# phase.net
KiCad netlist of a schematic drawn in Altium Designer
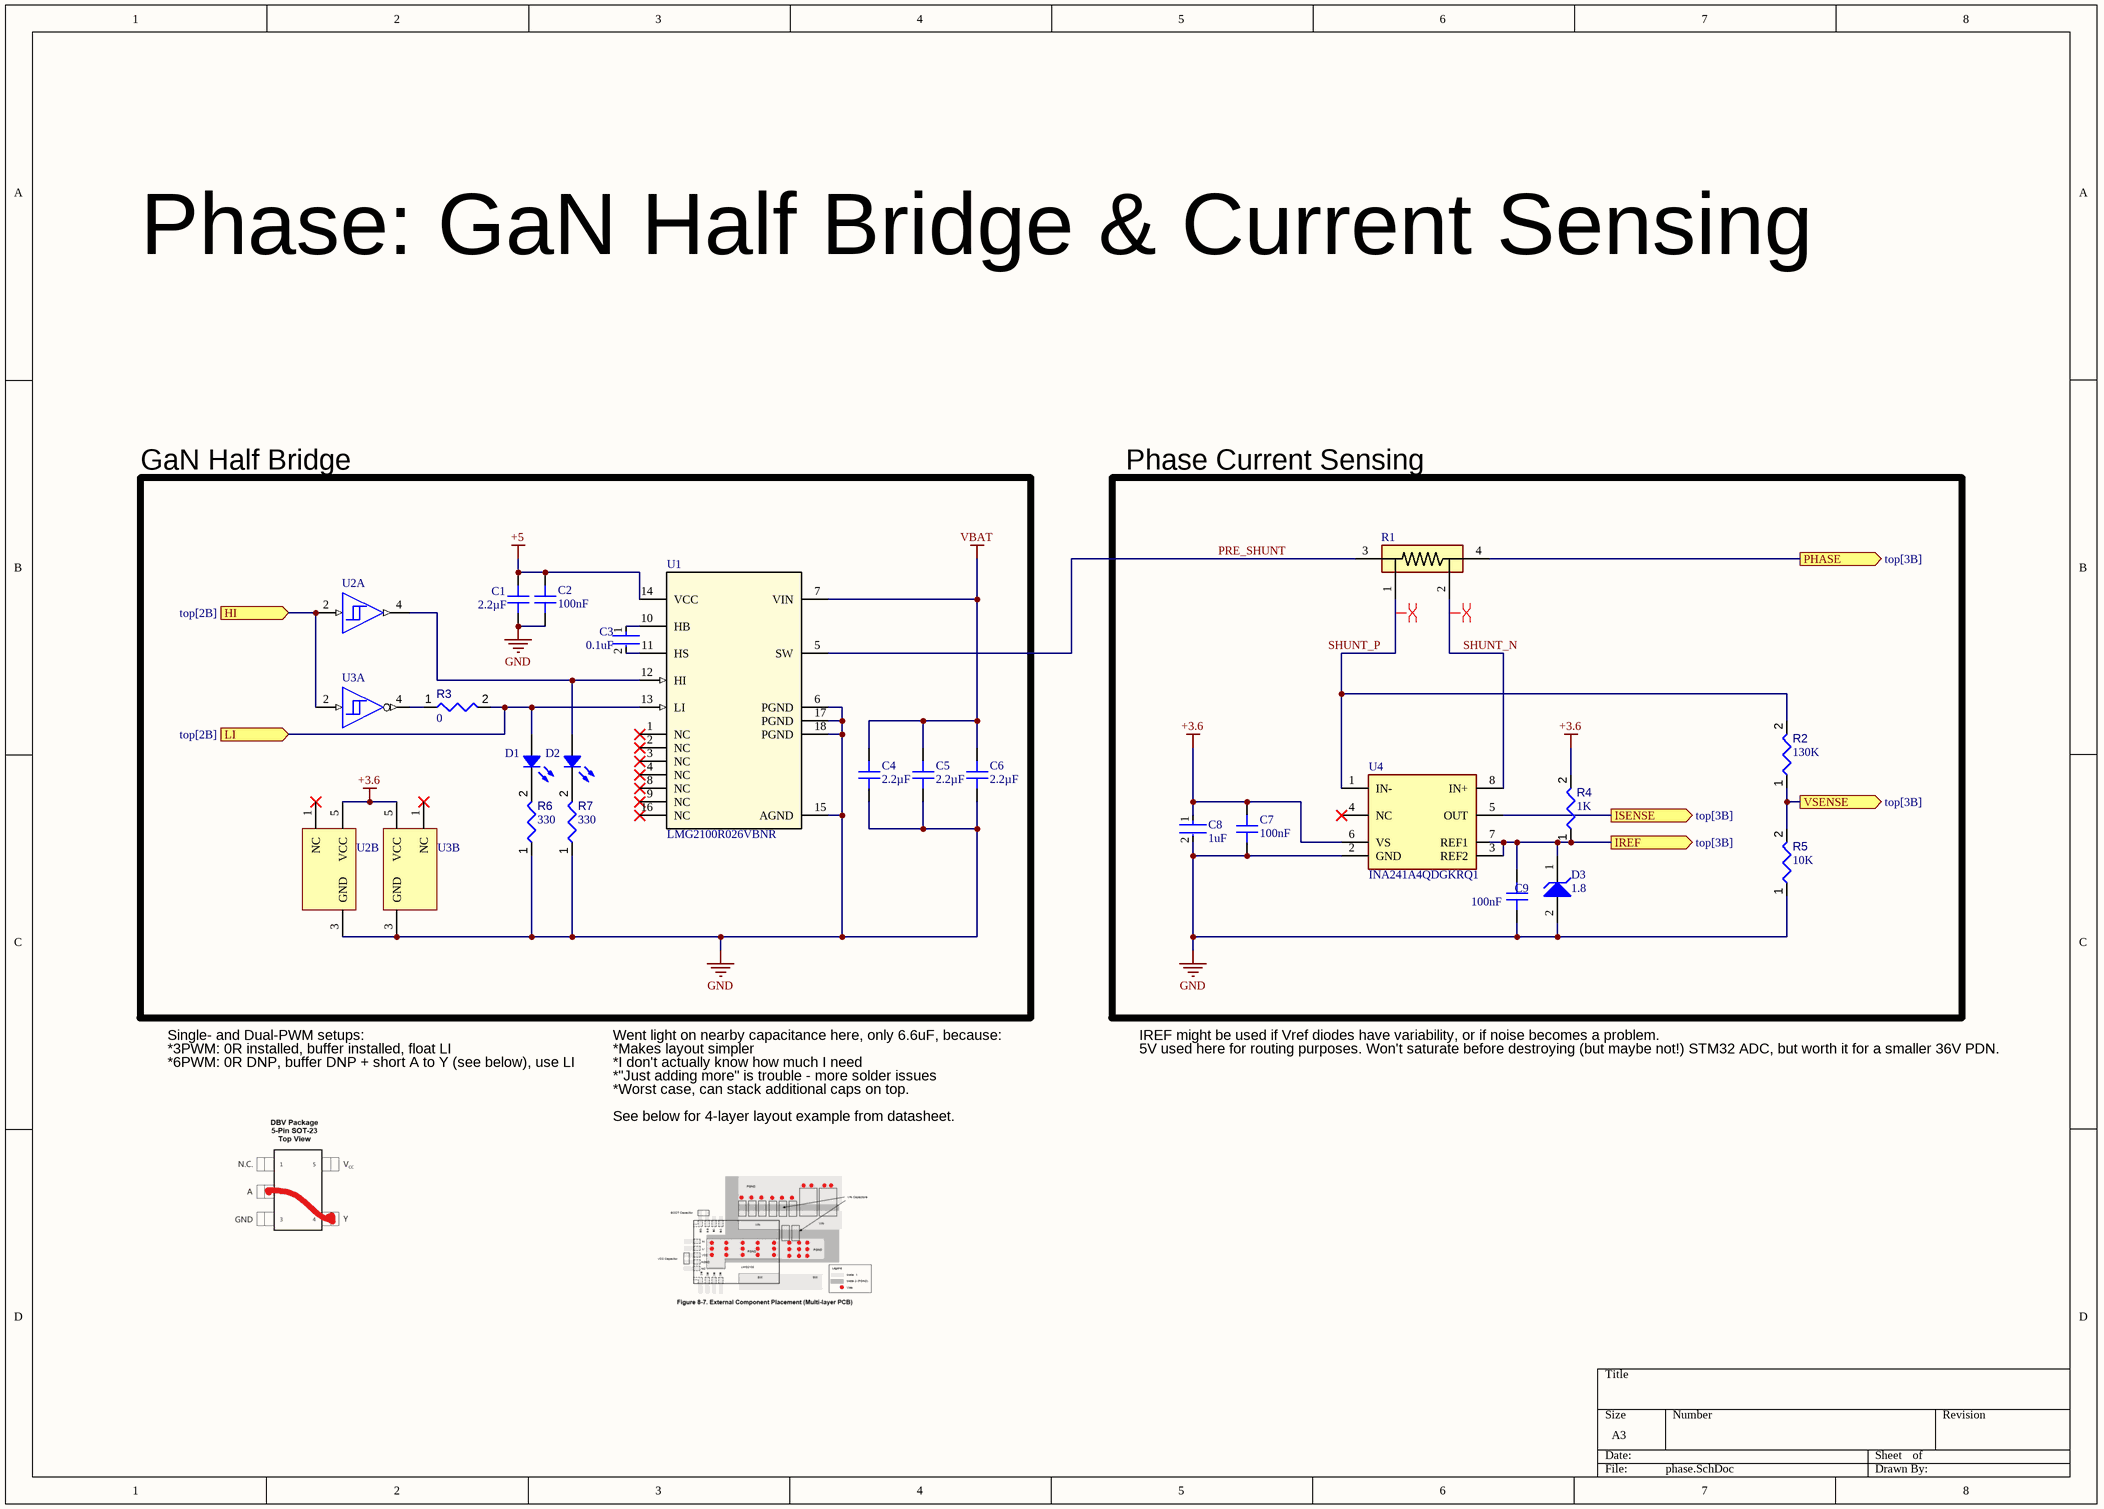
[diagram p0: phase.SchDoc]

(export (version "E")
  (design (tool "Eeschema 10.0.6"))
  (components
    (comp (ref "C1")
      (value "2.2µF")
      (footprint "CAP 0603_1608")
      (description "CAP CER 2.2UF 16V X5R 0603")
      (fields (field (name "PART NUMBER") "KGM15BR51C225KM") (field (name "TOLERANCE") "10%"))
      (libsource (lib "Americas- Northwestern Formula Racing- Northwestern University") (part "CAPACITOR"))
    )
    (comp (ref "C2")
      (value "100nF")
      (footprint "CAPC0402(1005)33_L")
      (description "CAP CER 0.1UF 16V X7R 0402")
      (fields
        (field (name "MANUFACTURER") "Samsung Electro-Mechanics")
        (field (name "PART NUMBER") "CL05B104KO5NNNC")
      )
      (libsource (lib "Americas- Northwestern Formula Racing- Northwestern University") (part "CAPACITOR"))
    )
    (comp (ref "C3")
      (value "0.1uF")
      (footprint "FP-GRM155-0_05-MFG")
      (description "Chip Multilayer Ceramic Capacitors for General Purpose, 0402, 1.0uF, B, 10%, 20%, 16V")
      (libsource (lib "Altium Content Vault") (part "02cd4be3c70576c341d710602a673aa"))
    )
    (comp (ref "C4")
      (value "2.2µF")
      (footprint "MURATA GRM21B 0805_2012")
      (description "CAP CER 2.2UF 100V X7T 0805")
      (fields (field (name "TOLERANCE") "20%") (field (name "MANUFACTURER") "Murata Electronics"))
      (libsource (lib "Americas- Northwestern Formula Racing- Northwestern University") (part "CAPACITOR"))
    )
    (comp (ref "C5")
      (value "2.2µF")
      (footprint "MURATA GRM21B 0805_2012")
      (description "CAP CER 2.2UF 100V X7T 0805")
      (fields (field (name "TOLERANCE") "20%") (field (name "MANUFACTURER") "Murata Electronics"))
      (libsource (lib "Americas- Northwestern Formula Racing- Northwestern University") (part "CAPACITOR"))
    )
    (comp (ref "C6")
      (value "2.2µF")
      (footprint "MURATA GRM21B 0805_2012")
      (description "CAP CER 2.2UF 100V X7T 0805")
      (fields (field (name "TOLERANCE") "20%") (field (name "MANUFACTURER") "Murata Electronics"))
      (libsource (lib "Americas- Northwestern Formula Racing- Northwestern University") (part "CAPACITOR"))
    )
    (comp (ref "C7")
      (value "100nF")
      (footprint "CAPC0402(1005)33_L")
      (description "CAP CER 0.1UF 16V X7R 0402")
      (fields
        (field (name "MANUFACTURER") "Samsung Electro-Mechanics")
        (field (name "PART NUMBER") "CL05B104KO5NNNC")
      )
      (libsource (lib "Americas- Northwestern Formula Racing- Northwestern University") (part "CAPACITOR"))
    )
    (comp (ref "C8")
      (value "1uF")
      (footprint "FP-GRM155-0_05-MFG")
      (description "Chip Multilayer Ceramic Capacitors for General Purpose, 0402, 1.0uF, B, 10%, 20%, 16V")
      (libsource (lib "Altium Content Vault") (part "02cd4be3c70576c341d710602a673aa"))
    )
    (comp (ref "C9")
      (value "100nF")
      (footprint "CAPC0402(1005)33_L")
      (description "CAP CER 0.1UF 16V X7R 0402")
      (fields
        (field (name "MANUFACTURER") "Samsung Electro-Mechanics")
        (field (name "PART NUMBER") "CL05B104KO5NNNC")
      )
      (libsource (lib "Americas- Northwestern Formula Racing- Northwestern University") (part "CAPACITOR"))
    )
    (comp (ref "D1")
      (value "150060BS55040")
      (footprint "LED 0603_1608 BLUE")
      (description "LED BLUE DIFFUSED 0603 SMD")
      (fields (field (name "MANUFACTURER") "Würth Elektronik"))
      (libsource (lib "Americas- Northwestern Formula Racing- Northwestern University") (part "LED"))
    )
    (comp (ref "D2")
      (value "150060BS55040")
      (footprint "LED 0603_1608 BLUE")
      (description "LED BLUE DIFFUSED 0603 SMD")
      (fields (field (name "MANUFACTURER") "Würth Elektronik"))
      (libsource (lib "Americas- Northwestern Formula Racing- Northwestern University") (part "LED"))
    )
    (comp (ref "D3")
      (value "SZMMSZ4678T1G")
      (footprint "ONSC-SOD-123-2-425-04_V")
      (description "Zener Voltage Regulator, 500 mW, 2-Pin SOD-123, Pb-Free, Tape and Reel")
      (fields (field (name "VZ TYP (V)") "1.8") (field (name "MANUFACTURER") "On Semiconductor"))
      (libsource (lib "Altium Content Vault") (part "ONSC-K1A2-2"))
    )
    (comp (ref "R1")
      (value "PU2726FKMPD0U3L")
      (footprint "PU2726FKMPD0U3L")
      (description "Thick Film Resistors - SMD 0.3mOhms 11W 2726 1% 75ppm Shunt AEC-Q200")
      (libsource (lib "Americas- Northwestern Formula Racing- Northwestern University") (part "PU2726FKMPD0U3L"))
    )
    (comp (ref "R2")
      (value "130K")
      (footprint "RESC0603(1608)_L")
      (description "120R 0.1W 5% 0603 (1608 Metric)  SMD")
      (fields (field (name "POWER") "100mW") (field (name "TOLERANCE") "5%"))
      (libsource (lib "Americas- Northwestern Formula Racing- Northwestern University") (part "120R3J"))
    )
    (comp (ref "R3")
      (value "0")
      (footprint "RESC0603(1608)_L")
      (description "Jumper 0603 (1608 Metric)")
      (fields (field (name "Comment") "0R3J"))
      (libsource (lib "Americas- Northwestern Formula Racing- Northwestern University") (part "0R3J"))
    )
    (comp (ref "R4")
      (value "1K")
      (footprint "RESC0603(1608)_L")
      (description "120R 0.1W 5% 0603 (1608 Metric)  SMD")
      (fields (field (name "POWER") "100mW") (field (name "TOLERANCE") "5%"))
      (libsource (lib "Americas- Northwestern Formula Racing- Northwestern University") (part "120R3J"))
    )
    (comp (ref "R5")
      (value "10K")
      (footprint "RESC0603(1608)_L")
      (description "120R 0.1W 5% 0603 (1608 Metric)  SMD")
      (fields (field (name "POWER") "100mW") (field (name "TOLERANCE") "5%"))
      (libsource (lib "Americas- Northwestern Formula Racing- Northwestern University") (part "120R3J"))
    )
    (comp (ref "R6")
      (value "330")
      (footprint "RESC0603(1608)_L")
      (description "120R 0.1W 5% 0603 (1608 Metric)  SMD")
      (fields (field (name "POWER") "100mW") (field (name "TOLERANCE") "5%"))
      (libsource (lib "Americas- Northwestern Formula Racing- Northwestern University") (part "120R3J"))
    )
    (comp (ref "R7")
      (value "330")
      (footprint "RESC0603(1608)_L")
      (description "120R 0.1W 5% 0603 (1608 Metric)  SMD")
      (fields (field (name "POWER") "100mW") (field (name "TOLERANCE") "5%"))
      (libsource (lib "Americas- Northwestern Formula Racing- Northwestern University") (part "120R3J"))
    )
    (comp (ref "U1")
      (value "LMG2100R026VBNR")
      (footprint "VBN0018A-MFG")
      (description "100V 2.6mOhm GaN half bridge module")
      (fields (field (name "COPYRIGHT") "Copyright (C) 2025 Ultra Librarian. All rights reserved."))
      (libsource (lib "Americas- Northwestern Formula Racing- Northwestern University") (part "LMG2100R026VBNR"))
    )
    (comp (ref "U2")
      (value "SN74AUP1G17DBVT")
      (footprint "DBV0005A_N")
      (description "Low-Power Single Schmitt-Trigger Buffer, DBV0005A, SMALL T&R")
      (fields
        (field (name "GENERIC PART NUMBER") "SN74AUP1G17")
        (field (name "MANUFACTURER") "Texas Instruments")
      )
      (libsource (lib "") (part "TI-SN74XXX1XXX-XX-5-SCHMITT_1"))
    )
    (comp (ref "U3")
      (value "SN74LVC1G14MDBVREP")
      (footprint "DBV0005A_N")
      (description "Enhanced Product Single Schmitt-Trigger Inverter, DBV0005A, LARGE T&R")
      (fields
        (field (name "GENERIC PART NUMBER") "SN74LVC1G14-EP")
        (field (name "MANUFACTURER") "Texas Instruments")
      )
      (libsource (lib "Altium Content Vault") (part "TI-SN74XXX1XX4-XX-5-SCHMITT"))
    )
    (comp (ref "U4")
      (value "INA241A4QDGKRQ1")
      (footprint "SOIC127P600X175-8N")
      (fields (field (name "MOUSER PART NUMBER") "595-INA241A4QDGKRQ1"))
      (libsource (lib "Americas- Northwestern Formula Racing- Northwestern University") (part "INA241A4QDGKRQ1"))
    )
  )
  (nets
    (net (code "1") (name "+3.6") (class "Default")
      (node (ref "C7") (pin "2") (pinfunction "2_2") (pintype "passive"))
      (node (ref "C8") (pin "1") (pinfunction "1_1") (pintype "passive"))
      (node (ref "R4") (pin "2") (pinfunction "2_2") (pintype "passive"))
      (node (ref "U2") (pin "5") (pinfunction "VCC_5") (pintype "power_in"))
      (node (ref "U3") (pin "5") (pinfunction "VCC_5") (pintype "power_in"))
      (node (ref "U4") (pin "6") (pinfunction "VS_6") (pintype "passive"))
    )
    (net (code "2") (name "+5") (class "Default")
      (node (ref "C1") (pin "2") (pinfunction "2_2") (pintype "passive"))
      (node (ref "C2") (pin "2") (pinfunction "2_2") (pintype "passive"))
      (node (ref "U1") (pin "14") (pinfunction "VCC_14") (pintype "power_in"))
    )
    (net (code "3") (name "/HI") (class "Default")
      (node (ref "U2") (pin "2") (pinfunction "A_2") (pintype "input"))
      (node (ref "U3") (pin "2") (pinfunction "A_2") (pintype "input"))
    )
    (net (code "4") (name "/IREF") (class "Default")
      (node (ref "C9") (pin "2") (pinfunction "2_2") (pintype "passive"))
      (node (ref "D3") (pin "1") (pinfunction "K_1") (pintype "passive"))
      (node (ref "R4") (pin "1") (pinfunction "1_1") (pintype "passive"))
      (node (ref "U4") (pin "3") (pinfunction "REF2_3") (pintype "passive"))
      (node (ref "U4") (pin "7") (pinfunction "REF1_7") (pintype "passive"))
    )
    (net (code "5") (name "/ISENSE") (class "Default")
      (node (ref "U4") (pin "5") (pinfunction "OUT_5") (pintype "passive"))
    )
    (net (code "6") (name "/LI") (class "Default")
      (node (ref "D1") (pin "1") (pinfunction "1_1") (pintype "passive"))
      (node (ref "R3") (pin "2") (pinfunction "2_2") (pintype "passive"))
      (node (ref "U1") (pin "13") (pinfunction "LI_13") (pintype "input"))
    )
    (net (code "7") (name "/PHASE") (class "Default")
      (node (ref "R1") (pin "4") (pinfunction "4_4") (pintype "passive"))
    )
    (net (code "8") (name "/PRE_SHUNT") (class "Default")
      (node (ref "R1") (pin "3") (pinfunction "3_3") (pintype "passive"))
      (node (ref "U1") (pin "5") (pinfunction "SW_5") (pintype "passive"))
    )
    (net (code "9") (name "/SHUNT_N") (class "Default")
      (node (ref "R1") (pin "2") (pinfunction "2_2") (pintype "passive"))
      (node (ref "U4") (pin "8") (pinfunction "IN+_8") (pintype "passive"))
    )
    (net (code "10") (name "/SHUNT_P") (class "Default")
      (node (ref "R1") (pin "1") (pinfunction "1_1") (pintype "passive"))
      (node (ref "R2") (pin "2") (pinfunction "2_2") (pintype "passive"))
      (node (ref "U4") (pin "1") (pinfunction "IN-_1") (pintype "passive"))
    )
    (net (code "11") (name "/VSENSE") (class "Default")
      (node (ref "R2") (pin "1") (pinfunction "1_1") (pintype "passive"))
      (node (ref "R5") (pin "2") (pinfunction "2_2") (pintype "passive"))
    )
    (net (code "12") (name "GND") (class "Default")
      (node (ref "C1") (pin "1") (pinfunction "1_1") (pintype "passive"))
      (node (ref "C2") (pin "1") (pinfunction "1_1") (pintype "passive"))
      (node (ref "C4") (pin "1") (pinfunction "1_1") (pintype "passive"))
      (node (ref "C5") (pin "1") (pinfunction "1_1") (pintype "passive"))
      (node (ref "C6") (pin "1") (pinfunction "1_1") (pintype "passive"))
      (node (ref "C7") (pin "1") (pinfunction "1_1") (pintype "passive"))
      (node (ref "C8") (pin "2") (pinfunction "2_2") (pintype "passive"))
      (node (ref "C9") (pin "1") (pinfunction "1_1") (pintype "passive"))
      (node (ref "D3") (pin "2") (pinfunction "A_2") (pintype "passive"))
      (node (ref "R5") (pin "1") (pinfunction "1_1") (pintype "passive"))
      (node (ref "R6") (pin "1") (pinfunction "1_1") (pintype "passive"))
      (node (ref "R7") (pin "1") (pinfunction "1_1") (pintype "passive"))
      (node (ref "U1") (pin "15") (pinfunction "AGND_15") (pintype "power_in"))
      (node (ref "U1") (pin "17") (pinfunction "PGND_17") (pintype "power_in"))
      (node (ref "U1") (pin "18") (pinfunction "PGND_18") (pintype "power_in"))
      (node (ref "U1") (pin "6") (pinfunction "PGND_6") (pintype "power_in"))
      (node (ref "U2") (pin "3") (pinfunction "GND_3") (pintype "power_in"))
      (node (ref "U3") (pin "3") (pinfunction "GND_3") (pintype "power_in"))
      (node (ref "U4") (pin "2") (pinfunction "GND_2") (pintype "passive"))
    )
    (net (code "13") (name "Net-(D1-Pad2)") (class "Default")
      (node (ref "D1") (pin "2") (pinfunction "2_2") (pintype "passive"))
      (node (ref "R6") (pin "2") (pinfunction "2_2") (pintype "passive"))
    )
    (net (code "14") (name "Net-(D2-Pad2)") (class "Default")
      (node (ref "D2") (pin "2") (pinfunction "2_2") (pintype "passive"))
      (node (ref "R7") (pin "2") (pinfunction "2_2") (pintype "passive"))
    )
    (net (code "15") (name "Net-(U1-HB)") (class "Default")
      (node (ref "C3") (pin "1") (pinfunction "1_1") (pintype "passive"))
      (node (ref "U1") (pin "10") (pinfunction "HB_10") (pintype "passive"))
    )
    (net (code "16") (name "Net-(U1-HI)") (class "Default")
      (node (ref "D2") (pin "1") (pinfunction "1_1") (pintype "passive"))
      (node (ref "U1") (pin "12") (pinfunction "HI_12") (pintype "input"))
      (node (ref "U2") (pin "4") (pinfunction "Y_4") (pintype "output"))
    )
    (net (code "17") (name "Net-(U1-HS)") (class "Default")
      (node (ref "C3") (pin "2") (pinfunction "2_2") (pintype "passive"))
      (node (ref "U1") (pin "11") (pinfunction "HS_11") (pintype "passive"))
    )
    (net (code "18") (name "Net-(U3A-Y)") (class "Default")
      (node (ref "R3") (pin "1") (pinfunction "1_1") (pintype "passive"))
      (node (ref "U3") (pin "4") (pinfunction "Y_4") (pintype "output"))
    )
    (net (code "19") (name "VBAT") (class "Default")
      (node (ref "C4") (pin "2") (pinfunction "2_2") (pintype "passive"))
      (node (ref "C5") (pin "2") (pinfunction "2_2") (pintype "passive"))
      (node (ref "C6") (pin "2") (pinfunction "2_2") (pintype "passive"))
      (node (ref "U1") (pin "7") (pinfunction "VIN_7") (pintype "power_in"))
    )
    (net (code "20") (name "unconnected-(U1-NC-Pad1)") (class "Default")
      (node (ref "U1") (pin "1") (pinfunction "NC_1") (pintype "passive+no_connect"))
    )
    (net (code "21") (name "unconnected-(U1-NC-Pad2)") (class "Default")
      (node (ref "U1") (pin "2") (pinfunction "NC_2") (pintype "passive+no_connect"))
    )
    (net (code "22") (name "unconnected-(U1-NC-Pad3)") (class "Default")
      (node (ref "U1") (pin "3") (pinfunction "NC_3") (pintype "passive+no_connect"))
    )
    (net (code "23") (name "unconnected-(U1-NC-Pad4)") (class "Default")
      (node (ref "U1") (pin "4") (pinfunction "NC_4") (pintype "passive+no_connect"))
    )
    (net (code "24") (name "unconnected-(U1-NC-Pad8)") (class "Default")
      (node (ref "U1") (pin "8") (pinfunction "NC_8") (pintype "passive+no_connect"))
    )
    (net (code "25") (name "unconnected-(U1-NC-Pad9)") (class "Default")
      (node (ref "U1") (pin "9") (pinfunction "NC_9") (pintype "passive+no_connect"))
    )
    (net (code "26") (name "unconnected-(U1-NC-Pad16)") (class "Default")
      (node (ref "U1") (pin "16") (pinfunction "NC_16") (pintype "passive+no_connect"))
    )
    (net (code "27") (name "unconnected-(U2B-NC-Pad1)") (class "Default")
      (node (ref "U2") (pin "1") (pinfunction "NC_1") (pintype "passive+no_connect"))
    )
    (net (code "28") (name "unconnected-(U3B-NC-Pad1)") (class "Default")
      (node (ref "U3") (pin "1") (pinfunction "NC_1") (pintype "passive+no_connect"))
    )
    (net (code "29") (name "unconnected-(U4-NC-Pad4)") (class "Default")
      (node (ref "U4") (pin "4") (pinfunction "NC_4") (pintype "passive+no_connect"))
    )
  )
)
